# RadioMusic_F_rev2-1.net
KiCad netlist of a schematic drawn in EAGLE
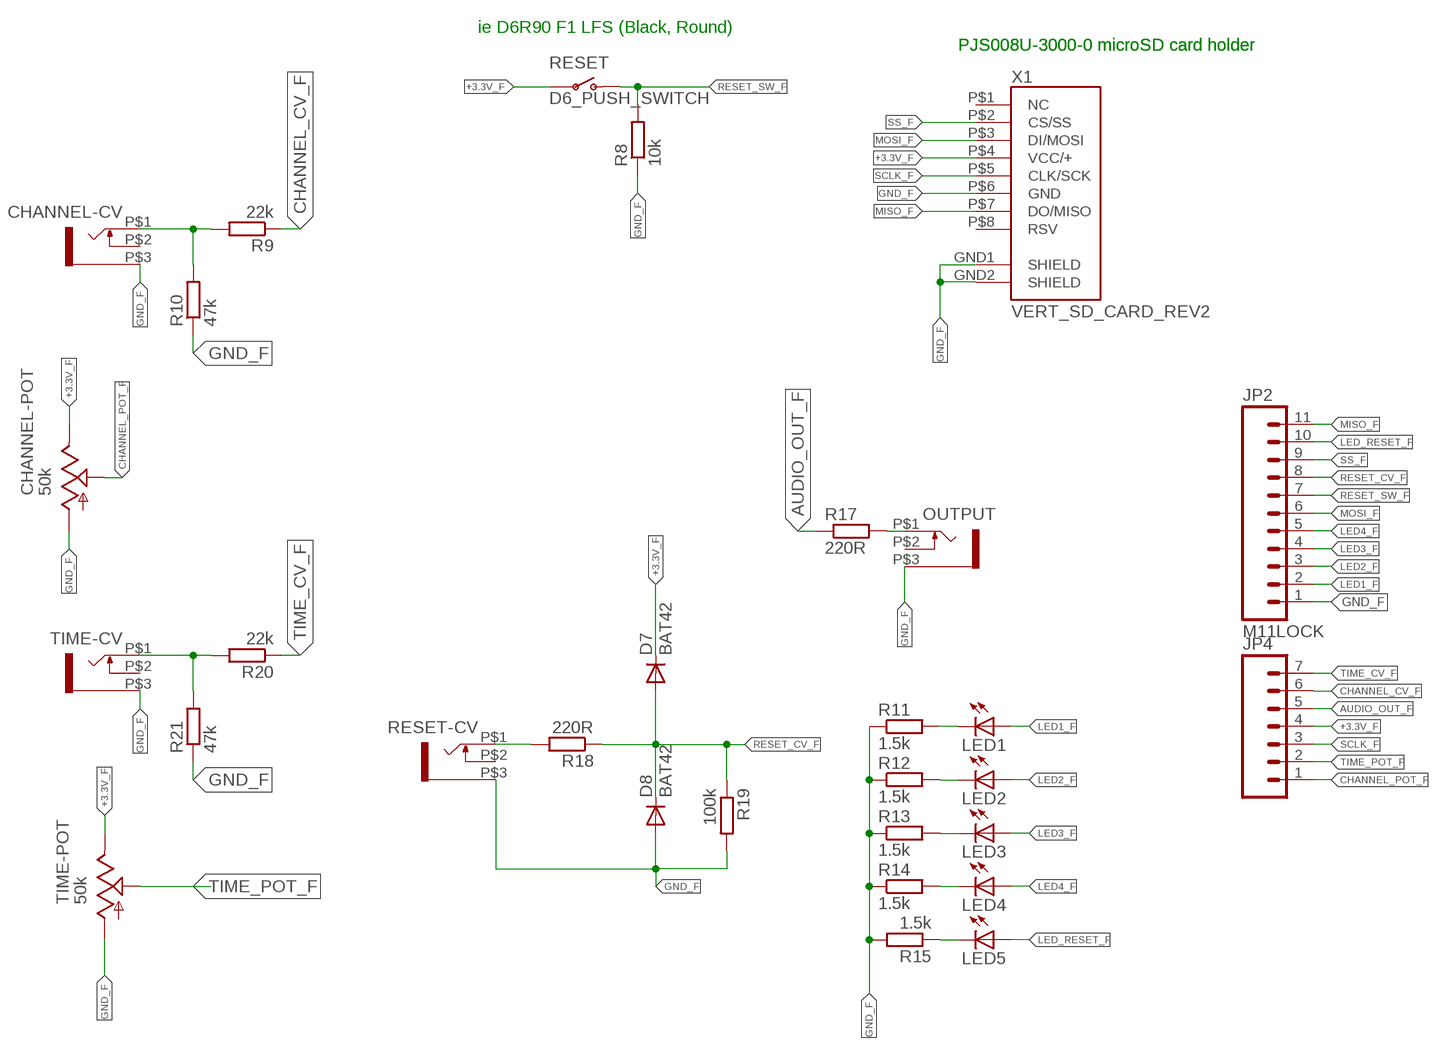
[diagram p0: schematic, sheet 1]

(export (version "E")
  (design (tool "Eeschema 10.0.6"))
  (components
    (comp (ref "CHANNEL-CV")
      (value "WQP-PJ301M-12_JACK")
      (footprint "eagle-import:WQP-PJ301M-12_JACK")
      (libsource (lib "eagle-import") (part "WQP-PJ301M-12_JACK"))
    )
    (comp (ref "CHANNEL-POT")
      (value "50k")
      (footprint "eagle-import:EVUF")
      (libsource (lib "eagle-import") (part "ALPHA-9MMAF2"))
    )
    (comp (ref "D7")
      (value "BAT42")
      (footprint "eagle-import:DO34-7")
      (libsource (lib "eagle-import") (part "BAT81"))
    )
    (comp (ref "D8")
      (value "BAT42")
      (footprint "eagle-import:DO34-7")
      (libsource (lib "eagle-import") (part "BAT81"))
    )
    (comp (ref "JP2")
      (value "M11LOCK")
      (footprint "eagle-import:1X11_LOCK")
      (libsource (lib "eagle-import") (part "M11LOCK"))
    )
    (comp (ref "JP4")
      (value "M07LOCK")
      (footprint "eagle-import:1X07_LOCK")
      (libsource (lib "eagle-import") (part "M07LOCK"))
    )
    (comp (ref "LED1")
      (value "LED3MM")
      (footprint "eagle-import:LED3MM")
      (libsource (lib "eagle-import") (part "LED3MM"))
    )
    (comp (ref "LED2")
      (value "LED3MM")
      (footprint "eagle-import:LED3MM")
      (libsource (lib "eagle-import") (part "LED3MM"))
    )
    (comp (ref "LED3")
      (value "LED3MM")
      (footprint "eagle-import:LED3MM")
      (libsource (lib "eagle-import") (part "LED3MM"))
    )
    (comp (ref "LED4")
      (value "LED3MM")
      (footprint "eagle-import:LED3MM")
      (libsource (lib "eagle-import") (part "LED3MM"))
    )
    (comp (ref "LED5")
      (value "LED3MM")
      (footprint "eagle-import:LED3MM")
      (libsource (lib "eagle-import") (part "LED3MM"))
    )
    (comp (ref "OUTPUT")
      (value "WQP-PJ301M-12_JACK")
      (footprint "eagle-import:WQP-PJ301M-12_JACK")
      (libsource (lib "eagle-import") (part "WQP-PJ301M-12_JACK"))
    )
    (comp (ref "R8")
      (value "10k")
      (footprint "eagle-import:0207_10")
      (libsource (lib "eagle-import") (part "R-EU_STANDARD_RESISTOR"))
    )
    (comp (ref "R9")
      (value "22k")
      (footprint "eagle-import:0207_10")
      (libsource (lib "eagle-import") (part "R-EU_STANDARD_RESISTOR"))
    )
    (comp (ref "R10")
      (value "47k")
      (footprint "eagle-import:0207_10")
      (libsource (lib "eagle-import") (part "R-EU_STANDARD_RESISTOR"))
    )
    (comp (ref "R11")
      (value "1.5k")
      (footprint "eagle-import:0207_10")
      (libsource (lib "eagle-import") (part "R-EU_STANDARD_RESISTOR"))
    )
    (comp (ref "R12")
      (value "1.5k")
      (footprint "eagle-import:0207_10")
      (libsource (lib "eagle-import") (part "R-EU_STANDARD_RESISTOR"))
    )
    (comp (ref "R13")
      (value "1.5k")
      (footprint "eagle-import:0207_10")
      (libsource (lib "eagle-import") (part "R-EU_STANDARD_RESISTOR"))
    )
    (comp (ref "R14")
      (value "1.5k")
      (footprint "eagle-import:0207_10")
      (libsource (lib "eagle-import") (part "R-EU_STANDARD_RESISTOR"))
    )
    (comp (ref "R15")
      (value "1.5k")
      (footprint "eagle-import:0207_10")
      (libsource (lib "eagle-import") (part "R-EU_STANDARD_RESISTOR"))
    )
    (comp (ref "R17")
      (value "220R")
      (footprint "eagle-import:0207_10")
      (libsource (lib "eagle-import") (part "R-EU_STANDARD_RESISTOR"))
    )
    (comp (ref "R18")
      (value "220R")
      (footprint "eagle-import:0207_10")
      (libsource (lib "eagle-import") (part "R-EU_STANDARD_RESISTOR"))
    )
    (comp (ref "R19")
      (value "100k")
      (footprint "eagle-import:0207_10")
      (libsource (lib "eagle-import") (part "R-EU_STANDARD_RESISTOR"))
    )
    (comp (ref "R20")
      (value "22k")
      (footprint "eagle-import:0207_10")
      (libsource (lib "eagle-import") (part "R-EU_STANDARD_RESISTOR"))
    )
    (comp (ref "R21")
      (value "47k")
      (footprint "eagle-import:0207_10")
      (libsource (lib "eagle-import") (part "R-EU_STANDARD_RESISTOR"))
    )
    (comp (ref "RESET")
      (value "D6_PUSH_SWITCH")
      (footprint "eagle-import:D6_BUTTON_RND")
      (libsource (lib "eagle-import") (part "D6_PUSH_SWITCH"))
    )
    (comp (ref "RESET-CV")
      (value "WQP-PJ301M-12_JACK")
      (footprint "eagle-import:WQP-PJ301M-12_JACK")
      (libsource (lib "eagle-import") (part "WQP-PJ301M-12_JACK"))
    )
    (comp (ref "TIME-CV")
      (value "WQP-PJ301M-12_JACK")
      (footprint "eagle-import:WQP-PJ301M-12_JACK")
      (libsource (lib "eagle-import") (part "WQP-PJ301M-12_JACK"))
    )
    (comp (ref "TIME-POT")
      (value "50k")
      (footprint "eagle-import:EVUF")
      (libsource (lib "eagle-import") (part "ALPHA-9MMAF2"))
    )
    (comp (ref "X1")
      (value "VERT_SD_CARD_REV2")
      (footprint "eagle-import:VERT_MICROSD_REV2")
      (libsource (lib "eagle-import") (part "VERT_SD_CARD_REV2"))
    )
  )
  (nets
    (net (code "1") (name "+3.3V_F") (class "Default")
      (node (ref "CHANNEL-POT") (pin "3") (pinfunction "E_3") (pintype "passive"))
      (node (ref "D7") (pin "C") (pinfunction "C_C") (pintype "passive"))
      (node (ref "JP4") (pin "4") (pinfunction "4_4") (pintype "passive"))
      (node (ref "RESET") (pin "P$3") (pinfunction "P_P$3") (pintype "passive"))
      (node (ref "RESET") (pin "P$4") (pinfunction "P_P$4") (pintype "passive"))
      (node (ref "TIME-POT") (pin "3") (pinfunction "E_3") (pintype "passive"))
      (node (ref "X1") (pin "P$4") (pinfunction "VCC/+_P$4") (pintype "bidirectional"))
    )
    (net (code "2") (name "AUDIO_OUT_F") (class "Default")
      (node (ref "JP4") (pin "5") (pinfunction "5_5") (pintype "passive"))
      (node (ref "R17") (pin "1") (pinfunction "1_1") (pintype "passive"))
    )
    (net (code "3") (name "CHANNEL_CV_F") (class "Default")
      (node (ref "JP4") (pin "6") (pinfunction "6_6") (pintype "passive"))
      (node (ref "R9") (pin "1") (pinfunction "1_1") (pintype "passive"))
    )
    (net (code "4") (name "CHANNEL_POT_F") (class "Default")
      (node (ref "CHANNEL-POT") (pin "2") (pinfunction "S_2") (pintype "passive"))
      (node (ref "JP4") (pin "1") (pinfunction "1_1") (pintype "passive"))
    )
    (net (code "5") (name "GND_F") (class "Default")
      (node (ref "CHANNEL-CV") (pin "P$3") (pinfunction "1_P$3") (pintype "passive"))
      (node (ref "CHANNEL-POT") (pin "1") (pinfunction "A_1") (pintype "passive"))
      (node (ref "D8") (pin "A") (pinfunction "A_A") (pintype "passive"))
      (node (ref "JP2") (pin "1") (pinfunction "1_1") (pintype "passive"))
      (node (ref "OUTPUT") (pin "P$3") (pinfunction "1_P$3") (pintype "passive"))
      (node (ref "R10") (pin "1") (pinfunction "1_1") (pintype "passive"))
      (node (ref "R11") (pin "1") (pinfunction "1_1") (pintype "passive"))
      (node (ref "R12") (pin "1") (pinfunction "1_1") (pintype "passive"))
      (node (ref "R13") (pin "1") (pinfunction "1_1") (pintype "passive"))
      (node (ref "R14") (pin "1") (pinfunction "1_1") (pintype "passive"))
      (node (ref "R15") (pin "2") (pinfunction "2_2") (pintype "passive"))
      (node (ref "R19") (pin "2") (pinfunction "2_2") (pintype "passive"))
      (node (ref "R21") (pin "1") (pinfunction "1_1") (pintype "passive"))
      (node (ref "R8") (pin "1") (pinfunction "1_1") (pintype "passive"))
      (node (ref "RESET-CV") (pin "P$3") (pinfunction "1_P$3") (pintype "passive"))
      (node (ref "TIME-CV") (pin "P$3") (pinfunction "1_P$3") (pintype "passive"))
      (node (ref "TIME-POT") (pin "1") (pinfunction "A_1") (pintype "passive"))
      (node (ref "X1") (pin "GND1") (pinfunction "SHIELD_GND1") (pintype "bidirectional"))
      (node (ref "X1") (pin "GND2") (pinfunction "SHIELD_GND2") (pintype "bidirectional"))
      (node (ref "X1") (pin "P$6") (pinfunction "GND_P$6") (pintype "bidirectional"))
    )
    (net (code "6") (name "LED1_F") (class "Default")
      (node (ref "JP2") (pin "2") (pinfunction "2_2") (pintype "passive"))
      (node (ref "LED1") (pin "A") (pinfunction "A_A") (pintype "passive"))
    )
    (net (code "7") (name "LED2_F") (class "Default")
      (node (ref "JP2") (pin "3") (pinfunction "3_3") (pintype "passive"))
      (node (ref "LED2") (pin "A") (pinfunction "A_A") (pintype "passive"))
    )
    (net (code "8") (name "LED3_F") (class "Default")
      (node (ref "JP2") (pin "4") (pinfunction "4_4") (pintype "passive"))
      (node (ref "LED3") (pin "A") (pinfunction "A_A") (pintype "passive"))
    )
    (net (code "9") (name "LED4_F") (class "Default")
      (node (ref "JP2") (pin "5") (pinfunction "5_5") (pintype "passive"))
      (node (ref "LED4") (pin "A") (pinfunction "A_A") (pintype "passive"))
    )
    (net (code "10") (name "LED_RESET_F") (class "Default")
      (node (ref "JP2") (pin "10") (pinfunction "10_10") (pintype "passive"))
      (node (ref "LED5") (pin "A") (pinfunction "A_A") (pintype "passive"))
    )
    (net (code "11") (name "MISO_F") (class "Default")
      (node (ref "JP2") (pin "11") (pinfunction "11_11") (pintype "passive"))
      (node (ref "X1") (pin "P$7") (pinfunction "DO/MISO_P$7") (pintype "bidirectional"))
    )
    (net (code "12") (name "MOSI_F") (class "Default")
      (node (ref "JP2") (pin "6") (pinfunction "6_6") (pintype "passive"))
      (node (ref "X1") (pin "P$3") (pinfunction "DI/MOSI_P$3") (pintype "bidirectional"))
    )
    (net (code "13") (name "Net-(CHANNEL-CV-2)") (class "Default")
      (node (ref "CHANNEL-CV") (pin "P$1") (pinfunction "2_P$1") (pintype "passive"))
      (node (ref "R10") (pin "2") (pinfunction "2_2") (pintype "passive"))
      (node (ref "R9") (pin "2") (pinfunction "2_2") (pintype "passive"))
    )
    (net (code "14") (name "Net-(LED1-C)") (class "Default")
      (node (ref "LED1") (pin "K") (pinfunction "C_K") (pintype "passive"))
      (node (ref "R11") (pin "2") (pinfunction "2_2") (pintype "passive"))
    )
    (net (code "15") (name "Net-(LED2-C)") (class "Default")
      (node (ref "LED2") (pin "K") (pinfunction "C_K") (pintype "passive"))
      (node (ref "R12") (pin "2") (pinfunction "2_2") (pintype "passive"))
    )
    (net (code "16") (name "Net-(LED3-C)") (class "Default")
      (node (ref "LED3") (pin "K") (pinfunction "C_K") (pintype "passive"))
      (node (ref "R13") (pin "2") (pinfunction "2_2") (pintype "passive"))
    )
    (net (code "17") (name "Net-(LED4-C)") (class "Default")
      (node (ref "LED4") (pin "K") (pinfunction "C_K") (pintype "passive"))
      (node (ref "R14") (pin "2") (pinfunction "2_2") (pintype "passive"))
    )
    (net (code "18") (name "Net-(LED5-C)") (class "Default")
      (node (ref "LED5") (pin "K") (pinfunction "C_K") (pintype "passive"))
      (node (ref "R15") (pin "1") (pinfunction "1_1") (pintype "passive"))
    )
    (net (code "19") (name "Net-(OUTPUT-2)") (class "Default")
      (node (ref "OUTPUT") (pin "P$1") (pinfunction "2_P$1") (pintype "passive"))
      (node (ref "R17") (pin "2") (pinfunction "2_2") (pintype "passive"))
    )
    (net (code "20") (name "Net-(RESET-CV-2)") (class "Default")
      (node (ref "R18") (pin "2") (pinfunction "2_2") (pintype "passive"))
      (node (ref "RESET-CV") (pin "P$1") (pinfunction "2_P$1") (pintype "passive"))
    )
    (net (code "21") (name "Net-(TIME-CV-2)") (class "Default")
      (node (ref "R20") (pin "2") (pinfunction "2_2") (pintype "passive"))
      (node (ref "R21") (pin "2") (pinfunction "2_2") (pintype "passive"))
      (node (ref "TIME-CV") (pin "P$1") (pinfunction "2_P$1") (pintype "passive"))
    )
    (net (code "22") (name "RESET_CV_F") (class "Default")
      (node (ref "D7") (pin "A") (pinfunction "A_A") (pintype "passive"))
      (node (ref "D8") (pin "C") (pinfunction "C_C") (pintype "passive"))
      (node (ref "JP2") (pin "8") (pinfunction "8_8") (pintype "passive"))
      (node (ref "R18") (pin "1") (pinfunction "1_1") (pintype "passive"))
      (node (ref "R19") (pin "1") (pinfunction "1_1") (pintype "passive"))
    )
    (net (code "23") (name "RESET_SW_F") (class "Default")
      (node (ref "JP2") (pin "7") (pinfunction "7_7") (pintype "passive"))
      (node (ref "R8") (pin "2") (pinfunction "2_2") (pintype "passive"))
      (node (ref "RESET") (pin "P$1") (pinfunction "O_P$1") (pintype "passive"))
      (node (ref "RESET") (pin "P$2") (pinfunction "O_P$2") (pintype "passive"))
    )
    (net (code "24") (name "SCLK_F") (class "Default")
      (node (ref "JP4") (pin "3") (pinfunction "3_3") (pintype "passive"))
      (node (ref "X1") (pin "P$5") (pinfunction "CLK/SCK_P$5") (pintype "bidirectional"))
    )
    (net (code "25") (name "SS_F") (class "Default")
      (node (ref "JP2") (pin "9") (pinfunction "9_9") (pintype "passive"))
      (node (ref "X1") (pin "P$2") (pinfunction "CS/SS_P$2") (pintype "bidirectional"))
    )
    (net (code "26") (name "TIME_CV_F") (class "Default")
      (node (ref "JP4") (pin "7") (pinfunction "7_7") (pintype "passive"))
      (node (ref "R20") (pin "1") (pinfunction "1_1") (pintype "passive"))
    )
    (net (code "27") (name "TIME_POT_F") (class "Default")
      (node (ref "JP4") (pin "2") (pinfunction "2_2") (pintype "passive"))
      (node (ref "TIME-POT") (pin "2") (pinfunction "S_2") (pintype "passive"))
    )
    (net (code "28") (name "unconnected-(CHANNEL-CV-3-PadP$2)") (class "Default")
      (node (ref "CHANNEL-CV") (pin "P$2") (pinfunction "3_P$2") (pintype "passive"))
    )
    (net (code "29") (name "unconnected-(OUTPUT-3-PadP$2)") (class "Default")
      (node (ref "OUTPUT") (pin "P$2") (pinfunction "3_P$2") (pintype "passive"))
    )
    (net (code "30") (name "unconnected-(RESET-CV-3-PadP$2)") (class "Default")
      (node (ref "RESET-CV") (pin "P$2") (pinfunction "3_P$2") (pintype "passive"))
    )
    (net (code "31") (name "unconnected-(TIME-CV-3-PadP$2)") (class "Default")
      (node (ref "TIME-CV") (pin "P$2") (pinfunction "3_P$2") (pintype "passive"))
    )
    (net (code "32") (name "unconnected-(X1-NC-PadP$1)") (class "Default")
      (node (ref "X1") (pin "P$1") (pinfunction "NC_P$1") (pintype "bidirectional"))
    )
    (net (code "33") (name "unconnected-(X1-RSV-PadP$8)") (class "Default")
      (node (ref "X1") (pin "P$8") (pinfunction "RSV_P$8") (pintype "bidirectional"))
    )
  )
)
